# attiny_tsop_adapter.net
KiCad netlist of a schematic drawn in EAGLE
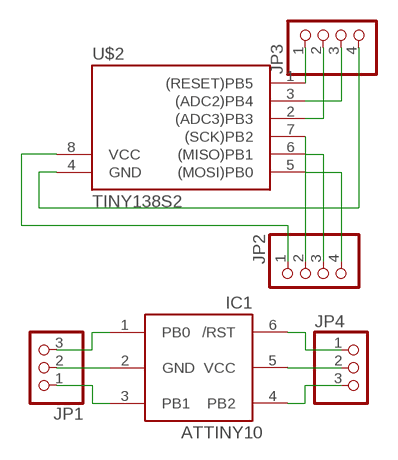
[diagram p0: schematic, sheet 1]

(export (version "E")
  (design (tool "Eeschema 10.0.6"))
  (components
    (comp (ref "IC1")
      (value "ATTINY10")
      (footprint "eagle-import:SOT23-6")
      (libsource (lib "eagle-import") (part "ATTINY10"))
    )
    (comp (ref "JP1")
      (value "PINHD-1X3")
      (footprint "eagle-import:1X03")
      (libsource (lib "eagle-import") (part "PINHD-1X3"))
    )
    (comp (ref "JP2")
      (value "PINHD-1X4")
      (footprint "eagle-import:1X04")
      (libsource (lib "eagle-import") (part "PINHD-1X4"))
    )
    (comp (ref "JP3")
      (value "PINHD-1X4")
      (footprint "eagle-import:1X04")
      (libsource (lib "eagle-import") (part "PINHD-1X4"))
    )
    (comp (ref "JP4")
      (value "PINHD-1X3")
      (footprint "eagle-import:1X03")
      (libsource (lib "eagle-import") (part "PINHD-1X3"))
    )
    (comp (ref "U$2")
      (value "TINY138S2")
      (footprint "eagle-import:SO08")
      (libsource (lib "eagle-import") (part "TINY138S2"))
    )
  )
  (nets
    (net (code "1") (name "Net-(IC1-GND)") (class "Default")
      (node (ref "IC1") (pin "2") (pinfunction "GND_2") (pintype "power_in"))
      (node (ref "JP1") (pin "2") (pinfunction "2_2") (pintype "passive"))
    )
    (net (code "2") (name "Net-(IC1-PB0)") (class "Default")
      (node (ref "IC1") (pin "1") (pinfunction "PB0_1") (pintype "bidirectional"))
      (node (ref "JP1") (pin "3") (pinfunction "3_3") (pintype "passive"))
    )
    (net (code "3") (name "Net-(IC1-PB1)") (class "Default")
      (node (ref "IC1") (pin "3") (pinfunction "PB1_3") (pintype "bidirectional"))
      (node (ref "JP1") (pin "1") (pinfunction "1_1") (pintype "passive"))
    )
    (net (code "4") (name "Net-(IC1-PB2)") (class "Default")
      (node (ref "IC1") (pin "4") (pinfunction "PB2_4") (pintype "bidirectional"))
      (node (ref "JP4") (pin "3") (pinfunction "3_3") (pintype "passive"))
    )
    (net (code "5") (name "Net-(IC1-VCC)") (class "Default")
      (node (ref "IC1") (pin "5") (pinfunction "VCC_5") (pintype "power_in"))
      (node (ref "JP4") (pin "2") (pinfunction "2_2") (pintype "passive"))
    )
    (net (code "6") (name "Net-(IC1-{slash}RST)") (class "Default")
      (node (ref "IC1") (pin "6") (pinfunction "/RST_6") (pintype "bidirectional"))
      (node (ref "JP4") (pin "1") (pinfunction "1_1") (pintype "passive"))
    )
    (net (code "7") (name "Net-(U$2-(ADC2)PB4)") (class "Default")
      (node (ref "JP3") (pin "3") (pinfunction "3_3") (pintype "passive"))
      (node (ref "U$2") (pin "3") (pinfunction "(ADC2)PB4_3") (pintype "bidirectional"))
    )
    (net (code "8") (name "Net-(U$2-(ADC3)PB3)") (class "Default")
      (node (ref "JP3") (pin "2") (pinfunction "2_2") (pintype "passive"))
      (node (ref "U$2") (pin "2") (pinfunction "(ADC3)PB3_2") (pintype "bidirectional"))
    )
    (net (code "9") (name "Net-(U$2-(MISO)PB1)") (class "Default")
      (node (ref "JP2") (pin "3") (pinfunction "3_3") (pintype "passive"))
      (node (ref "U$2") (pin "6") (pinfunction "(MISO)PB1_6") (pintype "bidirectional"))
    )
    (net (code "10") (name "Net-(U$2-(MOSI)PB0)") (class "Default")
      (node (ref "JP2") (pin "4") (pinfunction "4_4") (pintype "passive"))
      (node (ref "U$2") (pin "5") (pinfunction "(MOSI)PB0_5") (pintype "bidirectional"))
    )
    (net (code "11") (name "Net-(U$2-(RESET)PB5)") (class "Default")
      (node (ref "JP3") (pin "1") (pinfunction "1_1") (pintype "passive"))
      (node (ref "U$2") (pin "1") (pinfunction "(RESET)PB5_1") (pintype "bidirectional"))
    )
    (net (code "12") (name "Net-(U$2-(SCK)PB2)") (class "Default")
      (node (ref "JP2") (pin "2") (pinfunction "2_2") (pintype "passive"))
      (node (ref "U$2") (pin "7") (pinfunction "(SCK)PB2_7") (pintype "bidirectional"))
    )
    (net (code "13") (name "Net-(U$2-GND)") (class "Default")
      (node (ref "JP3") (pin "4") (pinfunction "4_4") (pintype "passive"))
      (node (ref "U$2") (pin "4") (pinfunction "GND_4") (pintype "power_in"))
    )
    (net (code "14") (name "Net-(U$2-VCC)") (class "Default")
      (node (ref "JP2") (pin "1") (pinfunction "1_1") (pintype "passive"))
      (node (ref "U$2") (pin "8") (pinfunction "VCC_8") (pintype "power_in"))
    )
  )
)
